# ioboard.net
KiCad netlist of a schematic drawn in EAGLE
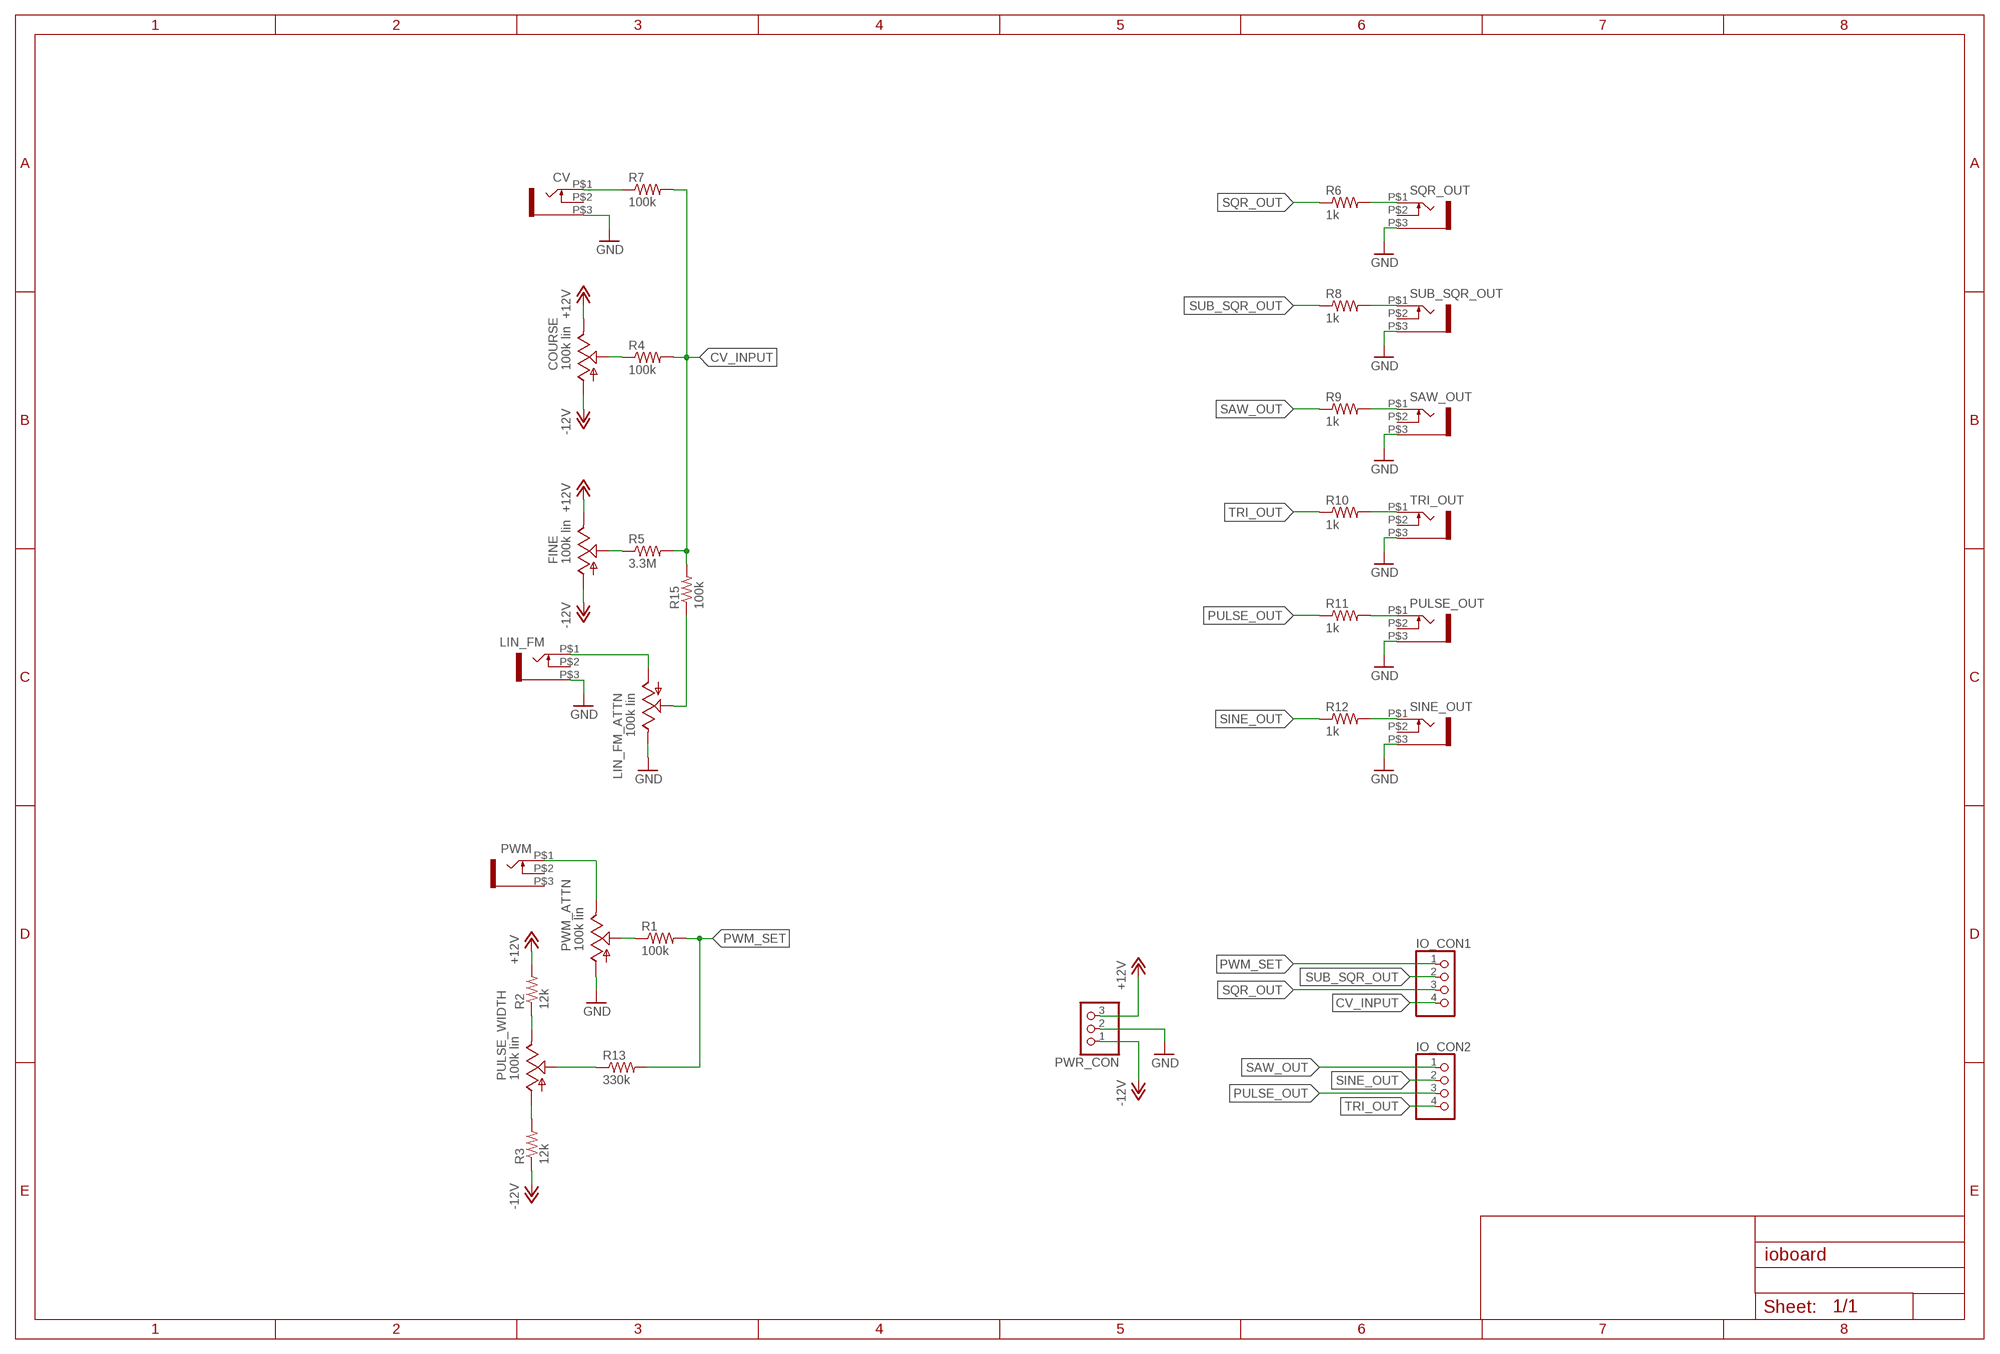
[diagram p0: schematic, sheet 1]

(export (version "E")
  (design (tool "Eeschema 10.0.6"))
  (components
    (comp (ref "COURSE")
      (value "100k lin")
      (footprint "eagle-import:EVUF")
      (libsource (lib "eagle-import") (part "ALPHA-9MMA"))
    )
    (comp (ref "CV")
      (value "WQP-PJ301M-12_JACK")
      (footprint "eagle-import:WQP-PJ301M-12_JACK")
      (libsource (lib "eagle-import") (part "WQP-PJ301M-12_JACK"))
    )
    (comp (ref "FINE")
      (value "100k lin")
      (footprint "eagle-import:EVUF")
      (libsource (lib "eagle-import") (part "ALPHA-9MMA"))
    )
    (comp (ref "IO_CON1")
      (value "PINHD-1X4")
      (footprint "eagle-import:1X04")
      (libsource (lib "eagle-import") (part "PINHD-1X4"))
    )
    (comp (ref "IO_CON2")
      (value "PINHD-1X4")
      (footprint "eagle-import:1X04")
      (libsource (lib "eagle-import") (part "PINHD-1X4"))
    )
    (comp (ref "LIN_FM")
      (value "WQP-PJ301M-12_JACK")
      (footprint "eagle-import:WQP-PJ301M-12_JACK")
      (libsource (lib "eagle-import") (part "WQP-PJ301M-12_JACK"))
    )
    (comp (ref "LIN_FM_ATTN")
      (value "100k lin")
      (footprint "eagle-import:EVUF")
      (libsource (lib "eagle-import") (part "ALPHA-9MMA"))
    )
    (comp (ref "PULSE_OUT")
      (value "WQP-PJ301M-12_JACK")
      (footprint "eagle-import:WQP-PJ301M-12_JACK")
      (libsource (lib "eagle-import") (part "WQP-PJ301M-12_JACK"))
    )
    (comp (ref "PULSE_WIDTH")
      (value "100k lin")
      (footprint "eagle-import:EVUF")
      (libsource (lib "eagle-import") (part "ALPHA-9MMA"))
    )
    (comp (ref "PWM")
      (value "WQP-PJ301M-12_JACK")
      (footprint "eagle-import:WQP-PJ301M-12_JACK")
      (libsource (lib "eagle-import") (part "WQP-PJ301M-12_JACK"))
    )
    (comp (ref "PWM_ATTN")
      (value "100k lin")
      (footprint "eagle-import:EVUF")
      (libsource (lib "eagle-import") (part "ALPHA-9MMA"))
    )
    (comp (ref "PWR_CON")
      (value "PINHD-1X3")
      (footprint "eagle-import:1X03")
      (libsource (lib "eagle-import") (part "PINHD-1X3"))
    )
    (comp (ref "R1")
      (value "100k")
      (footprint "eagle-import:0207_7")
      (libsource (lib "eagle-import") (part "R-US_0207/7"))
    )
    (comp (ref "R2")
      (value "12k")
      (footprint "eagle-import:0207_7")
      (libsource (lib "eagle-import") (part "R-US_0207/7"))
    )
    (comp (ref "R3")
      (value "12k")
      (footprint "eagle-import:0207_7")
      (libsource (lib "eagle-import") (part "R-US_0207/7"))
    )
    (comp (ref "R4")
      (value "100k")
      (footprint "eagle-import:0207_7")
      (libsource (lib "eagle-import") (part "R-US_0207/7"))
    )
    (comp (ref "R5")
      (value "3.3M")
      (footprint "eagle-import:0207_7")
      (libsource (lib "eagle-import") (part "R-US_0207/7"))
    )
    (comp (ref "R6")
      (value "1k")
      (footprint "eagle-import:0207_7")
      (libsource (lib "eagle-import") (part "R-US_0207/7"))
    )
    (comp (ref "R7")
      (value "100k")
      (footprint "eagle-import:0207_7")
      (libsource (lib "eagle-import") (part "R-US_0207/7"))
    )
    (comp (ref "R8")
      (value "1k")
      (footprint "eagle-import:0207_7")
      (libsource (lib "eagle-import") (part "R-US_0207/7"))
    )
    (comp (ref "R9")
      (value "1k")
      (footprint "eagle-import:0207_7")
      (libsource (lib "eagle-import") (part "R-US_0207/7"))
    )
    (comp (ref "R10")
      (value "1k")
      (footprint "eagle-import:0207_7")
      (libsource (lib "eagle-import") (part "R-US_0207/7"))
    )
    (comp (ref "R11")
      (value "1k")
      (footprint "eagle-import:0207_7")
      (libsource (lib "eagle-import") (part "R-US_0207/7"))
    )
    (comp (ref "R12")
      (value "1k")
      (footprint "eagle-import:0207_7")
      (libsource (lib "eagle-import") (part "R-US_0207/7"))
    )
    (comp (ref "R13")
      (value "330k")
      (footprint "eagle-import:0207_7")
      (libsource (lib "eagle-import") (part "R-US_0207/7"))
    )
    (comp (ref "R15")
      (value "100k")
      (footprint "eagle-import:0207_7")
      (libsource (lib "eagle-import") (part "R-US_0207/7"))
    )
    (comp (ref "SAW_OUT")
      (value "WQP-PJ301M-12_JACK")
      (footprint "eagle-import:WQP-PJ301M-12_JACK")
      (libsource (lib "eagle-import") (part "WQP-PJ301M-12_JACK"))
    )
    (comp (ref "SINE_OUT")
      (value "WQP-PJ301M-12_JACK")
      (footprint "eagle-import:WQP-PJ301M-12_JACK")
      (libsource (lib "eagle-import") (part "WQP-PJ301M-12_JACK"))
    )
    (comp (ref "SQR_OUT")
      (value "WQP-PJ301M-12_JACK")
      (footprint "eagle-import:WQP-PJ301M-12_JACK")
      (libsource (lib "eagle-import") (part "WQP-PJ301M-12_JACK"))
    )
    (comp (ref "SUB_SQR_OUT")
      (value "WQP-PJ301M-12_JACK")
      (footprint "eagle-import:WQP-PJ301M-12_JACK")
      (libsource (lib "eagle-import") (part "WQP-PJ301M-12_JACK"))
    )
    (comp (ref "TRI_OUT")
      (value "WQP-PJ301M-12_JACK")
      (footprint "eagle-import:WQP-PJ301M-12_JACK")
      (libsource (lib "eagle-import") (part "WQP-PJ301M-12_JACK"))
    )
  )
  (nets
    (net (code "1") (name "+12V") (class "Default")
      (node (ref "COURSE") (pin "3") (pinfunction "E_3") (pintype "passive"))
      (node (ref "FINE") (pin "3") (pinfunction "E_3") (pintype "passive"))
      (node (ref "PWR_CON") (pin "3") (pinfunction "3_3") (pintype "passive"))
      (node (ref "R2") (pin "2") (pinfunction "2_2") (pintype "passive"))
    )
    (net (code "2") (name "-12V") (class "Default")
      (node (ref "COURSE") (pin "1") (pinfunction "A_1") (pintype "passive"))
      (node (ref "FINE") (pin "1") (pinfunction "A_1") (pintype "passive"))
      (node (ref "PWR_CON") (pin "1") (pinfunction "1_1") (pintype "passive"))
      (node (ref "R3") (pin "1") (pinfunction "1_1") (pintype "passive"))
    )
    (net (code "3") (name "CV_INPUT") (class "Default")
      (node (ref "IO_CON1") (pin "4") (pinfunction "4_4") (pintype "passive"))
      (node (ref "R15") (pin "2") (pinfunction "2_2") (pintype "passive"))
      (node (ref "R4") (pin "2") (pinfunction "2_2") (pintype "passive"))
      (node (ref "R5") (pin "2") (pinfunction "2_2") (pintype "passive"))
      (node (ref "R7") (pin "2") (pinfunction "2_2") (pintype "passive"))
    )
    (net (code "4") (name "GND") (class "Default")
      (node (ref "CV") (pin "P$3") (pinfunction "1_P$3") (pintype "passive"))
      (node (ref "LIN_FM") (pin "P$3") (pinfunction "1_P$3") (pintype "passive"))
      (node (ref "LIN_FM_ATTN") (pin "3") (pinfunction "E_3") (pintype "passive"))
      (node (ref "PULSE_OUT") (pin "P$3") (pinfunction "1_P$3") (pintype "passive"))
      (node (ref "PWM_ATTN") (pin "1") (pinfunction "A_1") (pintype "passive"))
      (node (ref "PWR_CON") (pin "2") (pinfunction "2_2") (pintype "passive"))
      (node (ref "SAW_OUT") (pin "P$3") (pinfunction "1_P$3") (pintype "passive"))
      (node (ref "SINE_OUT") (pin "P$3") (pinfunction "1_P$3") (pintype "passive"))
      (node (ref "SQR_OUT") (pin "P$3") (pinfunction "1_P$3") (pintype "passive"))
      (node (ref "SUB_SQR_OUT") (pin "P$3") (pinfunction "1_P$3") (pintype "passive"))
      (node (ref "TRI_OUT") (pin "P$3") (pinfunction "1_P$3") (pintype "passive"))
    )
    (net (code "5") (name "Net-(COURSE-S)") (class "Default")
      (node (ref "COURSE") (pin "2") (pinfunction "S_2") (pintype "passive"))
      (node (ref "R4") (pin "1") (pinfunction "1_1") (pintype "passive"))
    )
    (net (code "6") (name "Net-(CV-2)") (class "Default")
      (node (ref "CV") (pin "P$1") (pinfunction "2_P$1") (pintype "passive"))
      (node (ref "R7") (pin "1") (pinfunction "1_1") (pintype "passive"))
    )
    (net (code "7") (name "Net-(FINE-S)") (class "Default")
      (node (ref "FINE") (pin "2") (pinfunction "S_2") (pintype "passive"))
      (node (ref "R5") (pin "1") (pinfunction "1_1") (pintype "passive"))
    )
    (net (code "8") (name "Net-(LIN_FM-2)") (class "Default")
      (node (ref "LIN_FM") (pin "P$1") (pinfunction "2_P$1") (pintype "passive"))
      (node (ref "LIN_FM_ATTN") (pin "1") (pinfunction "A_1") (pintype "passive"))
    )
    (net (code "9") (name "Net-(LIN_FM_ATTN-S)") (class "Default")
      (node (ref "LIN_FM_ATTN") (pin "2") (pinfunction "S_2") (pintype "passive"))
      (node (ref "R15") (pin "1") (pinfunction "1_1") (pintype "passive"))
    )
    (net (code "10") (name "Net-(PULSE_OUT-2)") (class "Default")
      (node (ref "PULSE_OUT") (pin "P$1") (pinfunction "2_P$1") (pintype "passive"))
      (node (ref "R11") (pin "2") (pinfunction "2_2") (pintype "passive"))
    )
    (net (code "11") (name "Net-(PULSE_WIDTH-A)") (class "Default")
      (node (ref "PULSE_WIDTH") (pin "1") (pinfunction "A_1") (pintype "passive"))
      (node (ref "R3") (pin "2") (pinfunction "2_2") (pintype "passive"))
    )
    (net (code "12") (name "Net-(PULSE_WIDTH-E)") (class "Default")
      (node (ref "PULSE_WIDTH") (pin "3") (pinfunction "E_3") (pintype "passive"))
      (node (ref "R2") (pin "1") (pinfunction "1_1") (pintype "passive"))
    )
    (net (code "13") (name "Net-(PULSE_WIDTH-S)") (class "Default")
      (node (ref "PULSE_WIDTH") (pin "2") (pinfunction "S_2") (pintype "passive"))
      (node (ref "R13") (pin "1") (pinfunction "1_1") (pintype "passive"))
    )
    (net (code "14") (name "Net-(PWM-2)") (class "Default")
      (node (ref "PWM") (pin "P$1") (pinfunction "2_P$1") (pintype "passive"))
      (node (ref "PWM_ATTN") (pin "3") (pinfunction "E_3") (pintype "passive"))
    )
    (net (code "15") (name "Net-(PWM_ATTN-S)") (class "Default")
      (node (ref "PWM_ATTN") (pin "2") (pinfunction "S_2") (pintype "passive"))
      (node (ref "R1") (pin "1") (pinfunction "1_1") (pintype "passive"))
    )
    (net (code "16") (name "Net-(SAW_OUT-2)") (class "Default")
      (node (ref "R9") (pin "2") (pinfunction "2_2") (pintype "passive"))
      (node (ref "SAW_OUT") (pin "P$1") (pinfunction "2_P$1") (pintype "passive"))
    )
    (net (code "17") (name "Net-(SINE_OUT-2)") (class "Default")
      (node (ref "R12") (pin "2") (pinfunction "2_2") (pintype "passive"))
      (node (ref "SINE_OUT") (pin "P$1") (pinfunction "2_P$1") (pintype "passive"))
    )
    (net (code "18") (name "Net-(SQR_OUT-2)") (class "Default")
      (node (ref "R6") (pin "2") (pinfunction "2_2") (pintype "passive"))
      (node (ref "SQR_OUT") (pin "P$1") (pinfunction "2_P$1") (pintype "passive"))
    )
    (net (code "19") (name "Net-(SUB_SQR_OUT-2)") (class "Default")
      (node (ref "R8") (pin "2") (pinfunction "2_2") (pintype "passive"))
      (node (ref "SUB_SQR_OUT") (pin "P$1") (pinfunction "2_P$1") (pintype "passive"))
    )
    (net (code "20") (name "Net-(TRI_OUT-2)") (class "Default")
      (node (ref "R10") (pin "2") (pinfunction "2_2") (pintype "passive"))
      (node (ref "TRI_OUT") (pin "P$1") (pinfunction "2_P$1") (pintype "passive"))
    )
    (net (code "21") (name "PULSE_OUT") (class "Default")
      (node (ref "IO_CON2") (pin "3") (pinfunction "3_3") (pintype "passive"))
      (node (ref "R11") (pin "1") (pinfunction "1_1") (pintype "passive"))
    )
    (net (code "22") (name "PWM_SET") (class "Default")
      (node (ref "IO_CON1") (pin "1") (pinfunction "1_1") (pintype "passive"))
      (node (ref "R1") (pin "2") (pinfunction "2_2") (pintype "passive"))
      (node (ref "R13") (pin "2") (pinfunction "2_2") (pintype "passive"))
    )
    (net (code "23") (name "SAW_OUT") (class "Default")
      (node (ref "IO_CON2") (pin "1") (pinfunction "1_1") (pintype "passive"))
      (node (ref "R9") (pin "1") (pinfunction "1_1") (pintype "passive"))
    )
    (net (code "24") (name "SINE_OUT") (class "Default")
      (node (ref "IO_CON2") (pin "2") (pinfunction "2_2") (pintype "passive"))
      (node (ref "R12") (pin "1") (pinfunction "1_1") (pintype "passive"))
    )
    (net (code "25") (name "SQR_OUT") (class "Default")
      (node (ref "IO_CON1") (pin "3") (pinfunction "3_3") (pintype "passive"))
      (node (ref "R6") (pin "1") (pinfunction "1_1") (pintype "passive"))
    )
    (net (code "26") (name "SUB_SQR_OUT") (class "Default")
      (node (ref "IO_CON1") (pin "2") (pinfunction "2_2") (pintype "passive"))
      (node (ref "R8") (pin "1") (pinfunction "1_1") (pintype "passive"))
    )
    (net (code "27") (name "TRI_OUT") (class "Default")
      (node (ref "IO_CON2") (pin "4") (pinfunction "4_4") (pintype "passive"))
      (node (ref "R10") (pin "1") (pinfunction "1_1") (pintype "passive"))
    )
    (net (code "28") (name "unconnected-(CV-3-PadP$2)") (class "Default")
      (node (ref "CV") (pin "P$2") (pinfunction "3_P$2") (pintype "passive"))
    )
    (net (code "29") (name "unconnected-(LIN_FM-3-PadP$2)") (class "Default")
      (node (ref "LIN_FM") (pin "P$2") (pinfunction "3_P$2") (pintype "passive"))
    )
    (net (code "30") (name "unconnected-(PULSE_OUT-3-PadP$2)") (class "Default")
      (node (ref "PULSE_OUT") (pin "P$2") (pinfunction "3_P$2") (pintype "passive"))
    )
    (net (code "31") (name "unconnected-(PWM-1-PadP$3)") (class "Default")
      (node (ref "PWM") (pin "P$3") (pinfunction "1_P$3") (pintype "passive"))
    )
    (net (code "32") (name "unconnected-(PWM-3-PadP$2)") (class "Default")
      (node (ref "PWM") (pin "P$2") (pinfunction "3_P$2") (pintype "passive"))
    )
    (net (code "33") (name "unconnected-(SAW_OUT-3-PadP$2)") (class "Default")
      (node (ref "SAW_OUT") (pin "P$2") (pinfunction "3_P$2") (pintype "passive"))
    )
    (net (code "34") (name "unconnected-(SINE_OUT-3-PadP$2)") (class "Default")
      (node (ref "SINE_OUT") (pin "P$2") (pinfunction "3_P$2") (pintype "passive"))
    )
    (net (code "35") (name "unconnected-(SQR_OUT-3-PadP$2)") (class "Default")
      (node (ref "SQR_OUT") (pin "P$2") (pinfunction "3_P$2") (pintype "passive"))
    )
    (net (code "36") (name "unconnected-(SUB_SQR_OUT-3-PadP$2)") (class "Default")
      (node (ref "SUB_SQR_OUT") (pin "P$2") (pinfunction "3_P$2") (pintype "passive"))
    )
    (net (code "37") (name "unconnected-(TRI_OUT-3-PadP$2)") (class "Default")
      (node (ref "TRI_OUT") (pin "P$2") (pinfunction "3_P$2") (pintype "passive"))
    )
  )
)
